# 2_74HC595_8.net
KiCad netlist of a schematic drawn in EasyEDA Pro
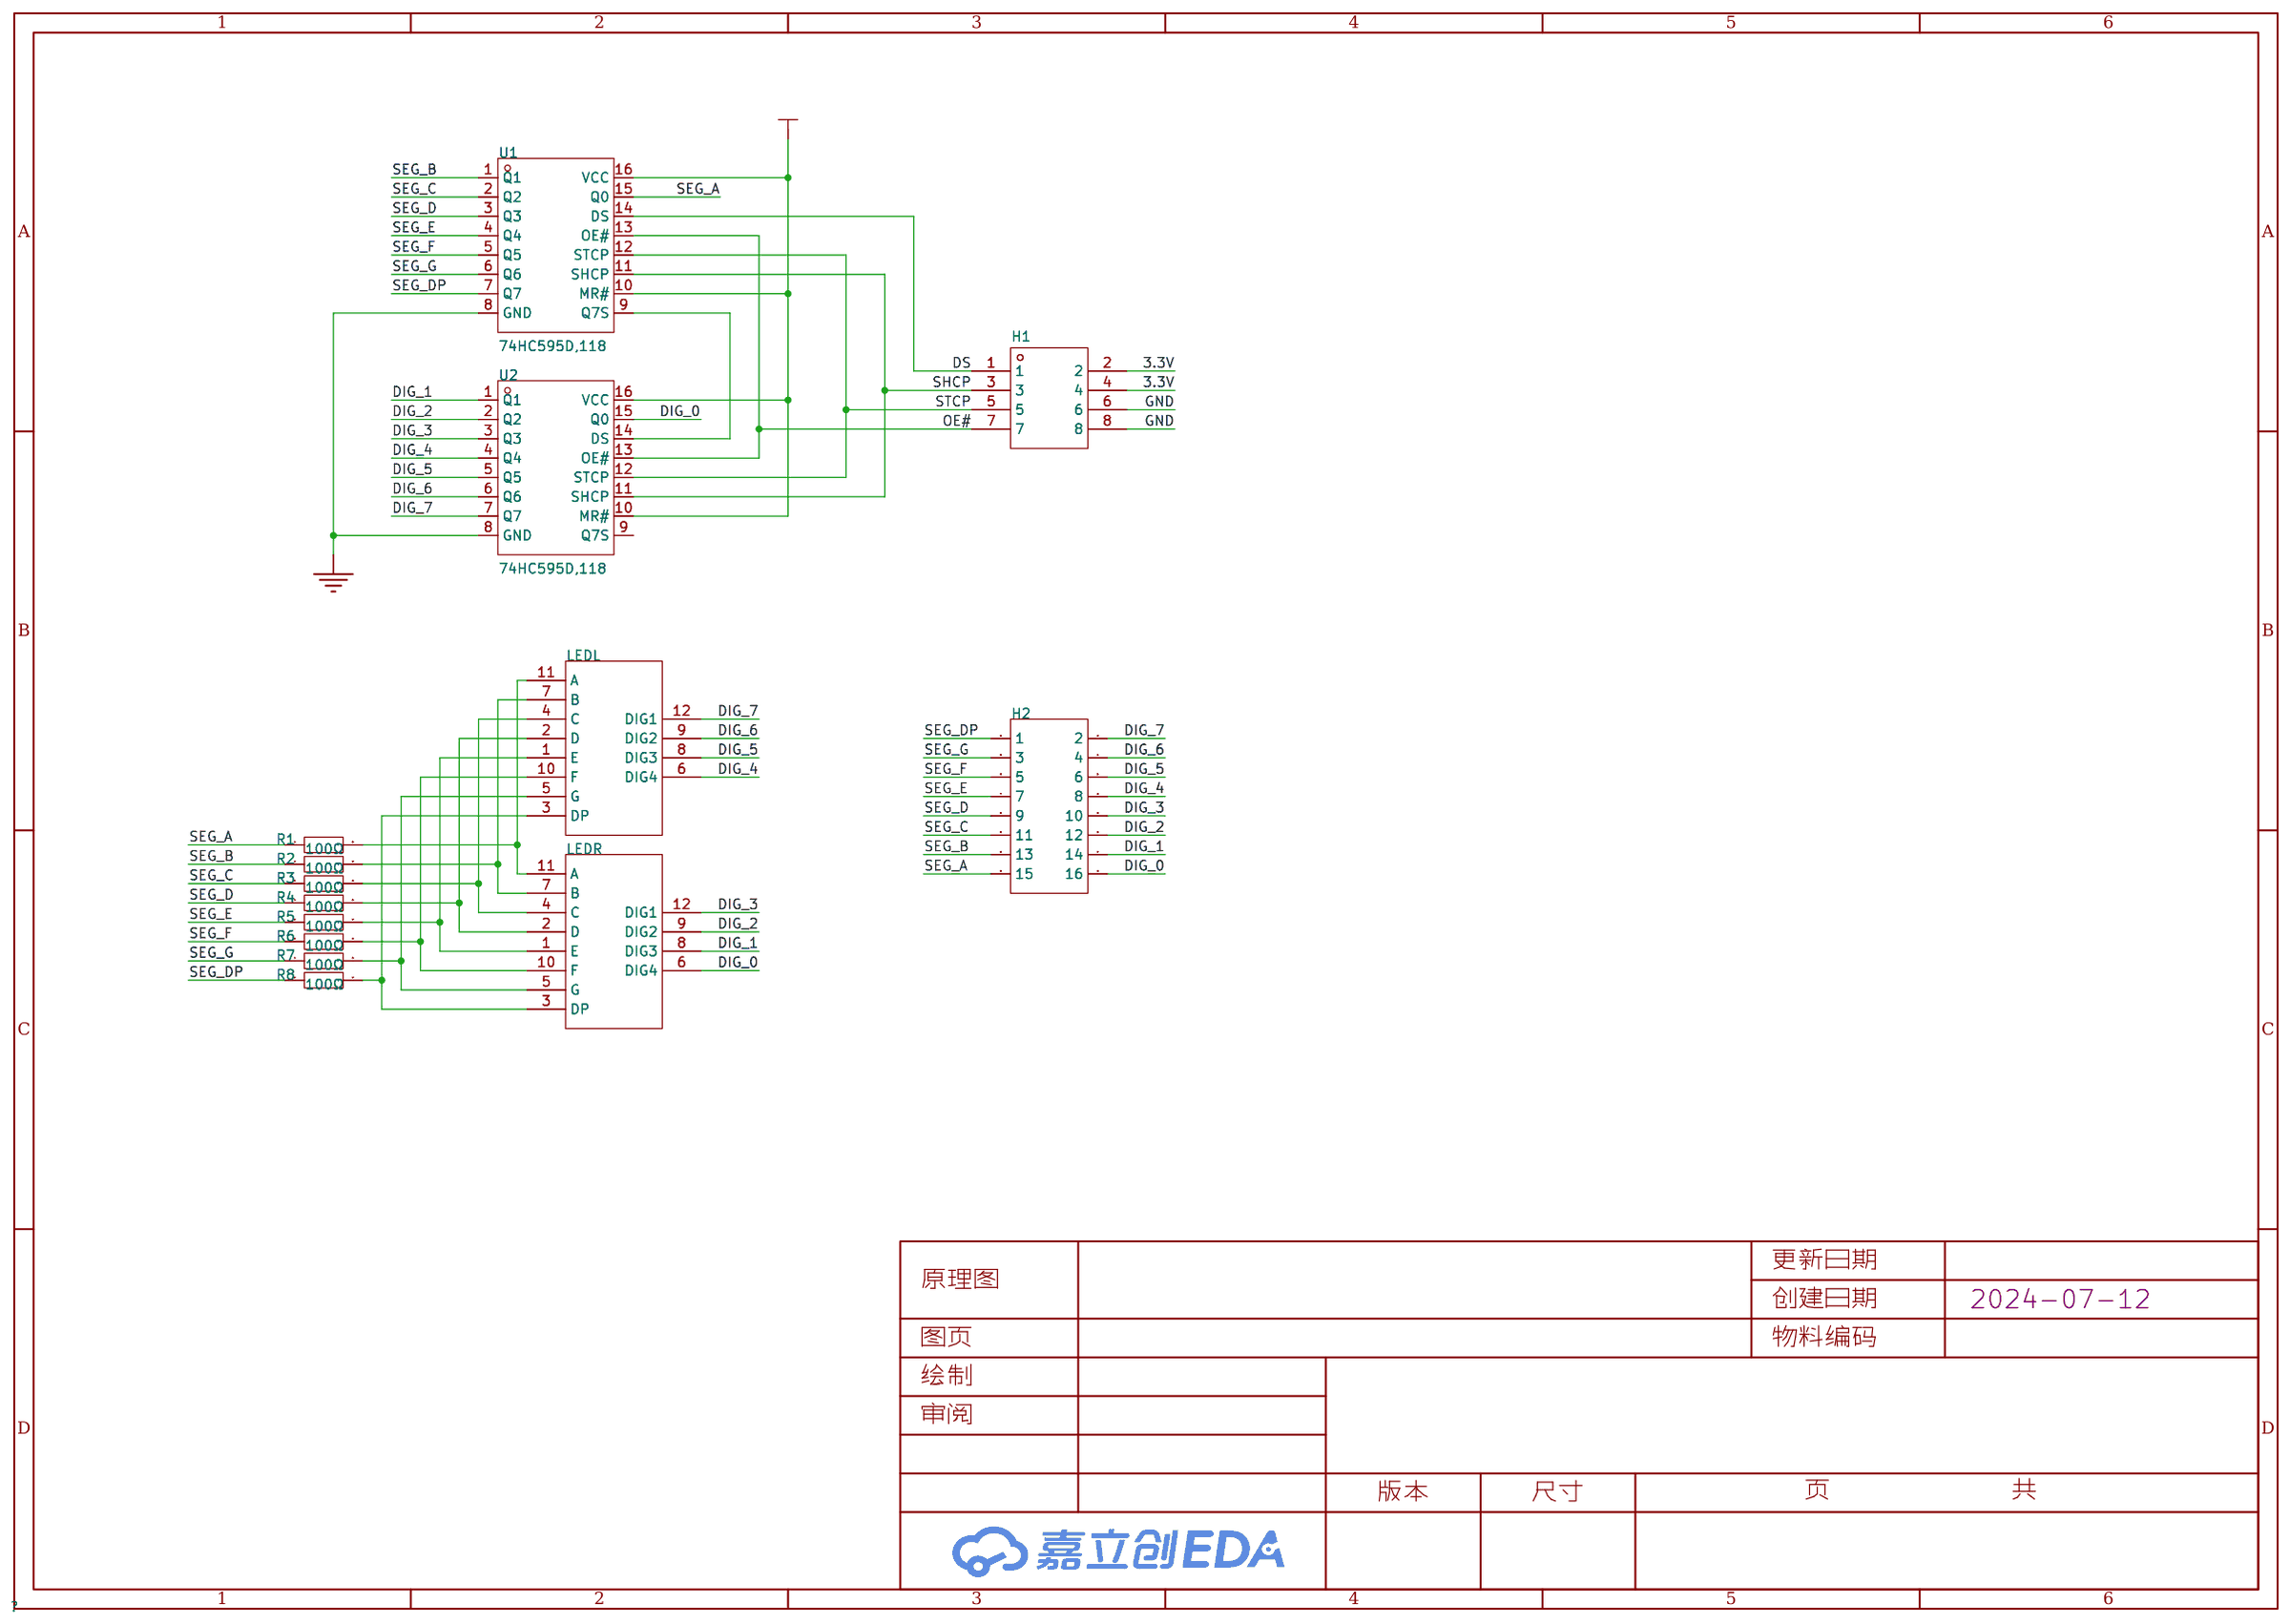
[diagram p0: schematic sheet]

(export (version "E")
  (design (tool "Eeschema 10.0.6"))
  (components
    (comp (ref "H1")
      (value "~")
      (footprint "easyedapro:HDR-TH_8P-P2.54-V-M-R2-C4-S2.54")
      (libsource (lib "easyedapro") (part "HDR-M-2.54_2x4"))
    )
    (comp (ref "H2")
      (value "~")
      (footprint "easyedapro:HDR-TH_16P-P2.54-V-M-R2-C8-S2.54")
      (libsource (lib "easyedapro") (part "HDR-M-2.54_2x8"))
    )
    (comp (ref "LEDL")
      (value "3461BS")
      (footprint "easyedapro:0.36inch_4bits_7seg_CA")
      (description "0.36英寸、四位、七段带小数点、共阳数码管")
      (libsource (lib "easyedapro") (part "0.36inch_4bits_7seg_CA"))
    )
    (comp (ref "LEDR")
      (value "3461BS")
      (footprint "easyedapro:0.36inch_4bits_7seg_CA")
      (description "0.36英寸、四位、七段带小数点、共阳数码管")
      (libsource (lib "easyedapro") (part "0.36inch_4bits_7seg_CA"))
    )
    (comp (ref "R1")
      (value "100Ω")
      (footprint "easyedapro:Res_1/4W")
      (libsource (lib "easyedapro") (part "电阻"))
    )
    (comp (ref "R2")
      (value "100Ω")
      (footprint "easyedapro:Res_1/4W")
      (libsource (lib "easyedapro") (part "电阻"))
    )
    (comp (ref "R3")
      (value "100Ω")
      (footprint "easyedapro:Res_1/4W")
      (libsource (lib "easyedapro") (part "电阻"))
    )
    (comp (ref "R4")
      (value "100Ω")
      (footprint "easyedapro:Res_1/4W")
      (libsource (lib "easyedapro") (part "电阻"))
    )
    (comp (ref "R5")
      (value "100Ω")
      (footprint "easyedapro:Res_1/4W")
      (libsource (lib "easyedapro") (part "电阻"))
    )
    (comp (ref "R6")
      (value "100Ω")
      (footprint "easyedapro:Res_1/4W")
      (libsource (lib "easyedapro") (part "电阻"))
    )
    (comp (ref "R7")
      (value "100Ω")
      (footprint "easyedapro:Res_1/4W")
      (libsource (lib "easyedapro") (part "电阻"))
    )
    (comp (ref "R8")
      (value "100Ω")
      (footprint "easyedapro:Res_1/4W")
      (libsource (lib "easyedapro") (part "电阻"))
    )
    (comp (ref "U1")
      (value "74HC595D,118")
      (footprint "easyedapro:SOIC-16_L9.9-W3.9-P1.27-LS6.0-BL")
      (description "功能:串行至串行或并行;电源电压:2V~6V;元件数:1;每个元件位数:8;")
      (fields (field (name "Manufacturer") "Nexperia(安世)"))
      (libsource (lib "easyedapro") (part "74HC595D,118"))
    )
    (comp (ref "U2")
      (value "74HC595D,118")
      (footprint "easyedapro:SOIC-16_L9.9-W3.9-P1.27-LS6.0-BL")
      (description "功能:串行至串行或并行;电源电压:2V~6V;元件数:1;每个元件位数:8;")
      (fields (field (name "Manufacturer") "Nexperia(安世)"))
      (libsource (lib "easyedapro") (part "74HC595D,118"))
    )
  )
  (nets
    (net (code "1") (name "/DIG_0") (class "Default")
      (node (ref "H2") (pin "16") (pinfunction "16_16") (pintype "input"))
      (node (ref "LEDR") (pin "6") (pinfunction "DIG4_6") (pintype "input"))
      (node (ref "U2") (pin "15") (pinfunction "Q0_15") (pintype "unspecified"))
    )
    (net (code "2") (name "/DIG_1") (class "Default")
      (node (ref "H2") (pin "14") (pinfunction "14_14") (pintype "input"))
      (node (ref "LEDR") (pin "8") (pinfunction "DIG3_8") (pintype "input"))
      (node (ref "U2") (pin "1") (pinfunction "Q1_1") (pintype "unspecified"))
    )
    (net (code "3") (name "/DIG_2") (class "Default")
      (node (ref "H2") (pin "12") (pinfunction "12_12") (pintype "input"))
      (node (ref "LEDR") (pin "9") (pinfunction "DIG2_9") (pintype "input"))
      (node (ref "U2") (pin "2") (pinfunction "Q2_2") (pintype "unspecified"))
    )
    (net (code "4") (name "/DIG_3") (class "Default")
      (node (ref "H2") (pin "10") (pinfunction "10_10") (pintype "input"))
      (node (ref "LEDR") (pin "12") (pinfunction "DIG1_12") (pintype "input"))
      (node (ref "U2") (pin "3") (pinfunction "Q3_3") (pintype "unspecified"))
    )
    (net (code "5") (name "/DIG_4") (class "Default")
      (node (ref "H2") (pin "8") (pinfunction "8_8") (pintype "input"))
      (node (ref "LEDL") (pin "6") (pinfunction "DIG4_6") (pintype "input"))
      (node (ref "U2") (pin "4") (pinfunction "Q4_4") (pintype "unspecified"))
    )
    (net (code "6") (name "/DIG_5") (class "Default")
      (node (ref "H2") (pin "6") (pinfunction "6_6") (pintype "input"))
      (node (ref "LEDL") (pin "8") (pinfunction "DIG3_8") (pintype "input"))
      (node (ref "U2") (pin "5") (pinfunction "Q5_5") (pintype "unspecified"))
    )
    (net (code "7") (name "/DIG_6") (class "Default")
      (node (ref "H2") (pin "4") (pinfunction "4_4") (pintype "input"))
      (node (ref "LEDL") (pin "9") (pinfunction "DIG2_9") (pintype "input"))
      (node (ref "U2") (pin "6") (pinfunction "Q6_6") (pintype "unspecified"))
    )
    (net (code "8") (name "/DIG_7") (class "Default")
      (node (ref "H2") (pin "2") (pinfunction "2_2") (pintype "input"))
      (node (ref "LEDL") (pin "12") (pinfunction "DIG1_12") (pintype "input"))
      (node (ref "U2") (pin "7") (pinfunction "Q7_7") (pintype "unspecified"))
    )
    (net (code "9") (name "/DS") (class "Default")
      (node (ref "H1") (pin "1") (pinfunction "1_1") (pintype "input"))
      (node (ref "U1") (pin "14") (pinfunction "DS_14") (pintype "unspecified"))
    )
    (net (code "10") (name "/OE#") (class "Default")
      (node (ref "H1") (pin "7") (pinfunction "7_7") (pintype "input"))
      (node (ref "U1") (pin "13") (pinfunction "OE#_13") (pintype "unspecified"))
      (node (ref "U2") (pin "13") (pinfunction "OE#_13") (pintype "unspecified"))
    )
    (net (code "11") (name "/SEG_A") (class "Default")
      (node (ref "H2") (pin "15") (pinfunction "15_15") (pintype "input"))
      (node (ref "R1") (pin "1") (pinfunction "1_1") (pintype "input"))
      (node (ref "U1") (pin "15") (pinfunction "Q0_15") (pintype "unspecified"))
    )
    (net (code "12") (name "/SEG_B") (class "Default")
      (node (ref "H2") (pin "13") (pinfunction "13_13") (pintype "input"))
      (node (ref "R2") (pin "1") (pinfunction "1_1") (pintype "input"))
      (node (ref "U1") (pin "1") (pinfunction "Q1_1") (pintype "unspecified"))
    )
    (net (code "13") (name "/SEG_C") (class "Default")
      (node (ref "H2") (pin "11") (pinfunction "11_11") (pintype "input"))
      (node (ref "R3") (pin "1") (pinfunction "1_1") (pintype "input"))
      (node (ref "U1") (pin "2") (pinfunction "Q2_2") (pintype "unspecified"))
    )
    (net (code "14") (name "/SEG_D") (class "Default")
      (node (ref "H2") (pin "9") (pinfunction "9_9") (pintype "input"))
      (node (ref "R4") (pin "1") (pinfunction "1_1") (pintype "input"))
      (node (ref "U1") (pin "3") (pinfunction "Q3_3") (pintype "unspecified"))
    )
    (net (code "15") (name "/SEG_DP") (class "Default")
      (node (ref "H2") (pin "1") (pinfunction "1_1") (pintype "input"))
      (node (ref "R8") (pin "1") (pinfunction "1_1") (pintype "input"))
      (node (ref "U1") (pin "7") (pinfunction "Q7_7") (pintype "unspecified"))
    )
    (net (code "16") (name "/SEG_E") (class "Default")
      (node (ref "H2") (pin "7") (pinfunction "7_7") (pintype "input"))
      (node (ref "R5") (pin "1") (pinfunction "1_1") (pintype "input"))
      (node (ref "U1") (pin "4") (pinfunction "Q4_4") (pintype "unspecified"))
    )
    (net (code "17") (name "/SEG_F") (class "Default")
      (node (ref "H2") (pin "5") (pinfunction "5_5") (pintype "input"))
      (node (ref "R6") (pin "1") (pinfunction "1_1") (pintype "input"))
      (node (ref "U1") (pin "5") (pinfunction "Q5_5") (pintype "unspecified"))
    )
    (net (code "18") (name "/SEG_G") (class "Default")
      (node (ref "H2") (pin "3") (pinfunction "3_3") (pintype "input"))
      (node (ref "R7") (pin "1") (pinfunction "1_1") (pintype "input"))
      (node (ref "U1") (pin "6") (pinfunction "Q6_6") (pintype "unspecified"))
    )
    (net (code "19") (name "/SHCP") (class "Default")
      (node (ref "H1") (pin "3") (pinfunction "3_3") (pintype "input"))
      (node (ref "U1") (pin "11") (pinfunction "SHCP_11") (pintype "unspecified"))
      (node (ref "U2") (pin "11") (pinfunction "SHCP_11") (pintype "unspecified"))
    )
    (net (code "20") (name "/STCP") (class "Default")
      (node (ref "H1") (pin "5") (pinfunction "5_5") (pintype "input"))
      (node (ref "U1") (pin "12") (pinfunction "STCP_12") (pintype "unspecified"))
      (node (ref "U2") (pin "12") (pinfunction "STCP_12") (pintype "unspecified"))
    )
    (net (code "21") (name "3.3V") (class "Default")
      (node (ref "H1") (pin "2") (pinfunction "2_2") (pintype "input"))
      (node (ref "H1") (pin "4") (pinfunction "4_4") (pintype "input"))
      (node (ref "U1") (pin "10") (pinfunction "MR#_10") (pintype "unspecified"))
      (node (ref "U1") (pin "16") (pinfunction "VCC_16") (pintype "unspecified"))
      (node (ref "U2") (pin "10") (pinfunction "MR#_10") (pintype "unspecified"))
      (node (ref "U2") (pin "16") (pinfunction "VCC_16") (pintype "unspecified"))
    )
    (net (code "22") (name "GND") (class "Default")
      (node (ref "H1") (pin "6") (pinfunction "6_6") (pintype "input"))
      (node (ref "H1") (pin "8") (pinfunction "8_8") (pintype "input"))
      (node (ref "U1") (pin "8") (pinfunction "GND_8") (pintype "unspecified"))
      (node (ref "U2") (pin "8") (pinfunction "GND_8") (pintype "unspecified"))
    )
    (net (code "23") (name "Net-(LEDL-A)") (class "Default")
      (node (ref "LEDL") (pin "11") (pinfunction "A_11") (pintype "input"))
      (node (ref "LEDR") (pin "11") (pinfunction "A_11") (pintype "input"))
      (node (ref "R1") (pin "2") (pinfunction "2_2") (pintype "input"))
    )
    (net (code "24") (name "Net-(LEDL-B)") (class "Default")
      (node (ref "LEDL") (pin "7") (pinfunction "B_7") (pintype "input"))
      (node (ref "LEDR") (pin "7") (pinfunction "B_7") (pintype "input"))
      (node (ref "R2") (pin "2") (pinfunction "2_2") (pintype "input"))
    )
    (net (code "25") (name "Net-(LEDL-C)") (class "Default")
      (node (ref "LEDL") (pin "4") (pinfunction "C_4") (pintype "input"))
      (node (ref "LEDR") (pin "4") (pinfunction "C_4") (pintype "input"))
      (node (ref "R3") (pin "2") (pinfunction "2_2") (pintype "input"))
    )
    (net (code "26") (name "Net-(LEDL-D)") (class "Default")
      (node (ref "LEDL") (pin "2") (pinfunction "D_2") (pintype "input"))
      (node (ref "LEDR") (pin "2") (pinfunction "D_2") (pintype "input"))
      (node (ref "R4") (pin "2") (pinfunction "2_2") (pintype "input"))
    )
    (net (code "27") (name "Net-(LEDL-DP)") (class "Default")
      (node (ref "LEDL") (pin "3") (pinfunction "DP_3") (pintype "input"))
      (node (ref "LEDR") (pin "3") (pinfunction "DP_3") (pintype "input"))
      (node (ref "R8") (pin "2") (pinfunction "2_2") (pintype "input"))
    )
    (net (code "28") (name "Net-(LEDL-E)") (class "Default")
      (node (ref "LEDL") (pin "1") (pinfunction "E_1") (pintype "input"))
      (node (ref "LEDR") (pin "1") (pinfunction "E_1") (pintype "input"))
      (node (ref "R5") (pin "2") (pinfunction "2_2") (pintype "input"))
    )
    (net (code "29") (name "Net-(LEDL-F)") (class "Default")
      (node (ref "LEDL") (pin "10") (pinfunction "F_10") (pintype "input"))
      (node (ref "LEDR") (pin "10") (pinfunction "F_10") (pintype "input"))
      (node (ref "R6") (pin "2") (pinfunction "2_2") (pintype "input"))
    )
    (net (code "30") (name "Net-(LEDL-G)") (class "Default")
      (node (ref "LEDL") (pin "5") (pinfunction "G_5") (pintype "input"))
      (node (ref "LEDR") (pin "5") (pinfunction "G_5") (pintype "input"))
      (node (ref "R7") (pin "2") (pinfunction "2_2") (pintype "input"))
    )
    (net (code "31") (name "Net-(U1-Q7S)") (class "Default")
      (node (ref "U1") (pin "9") (pinfunction "Q7S_9") (pintype "unspecified"))
      (node (ref "U2") (pin "14") (pinfunction "DS_14") (pintype "unspecified"))
    )
    (net (code "32") (name "unconnected-(U2-Q7S-Pad9)") (class "Default")
      (node (ref "U2") (pin "9") (pinfunction "Q7S_9") (pintype "unspecified"))
    )
  )
)
